# placa-endstops.net
KiCad netlist of a schematic drawn in EAGLE
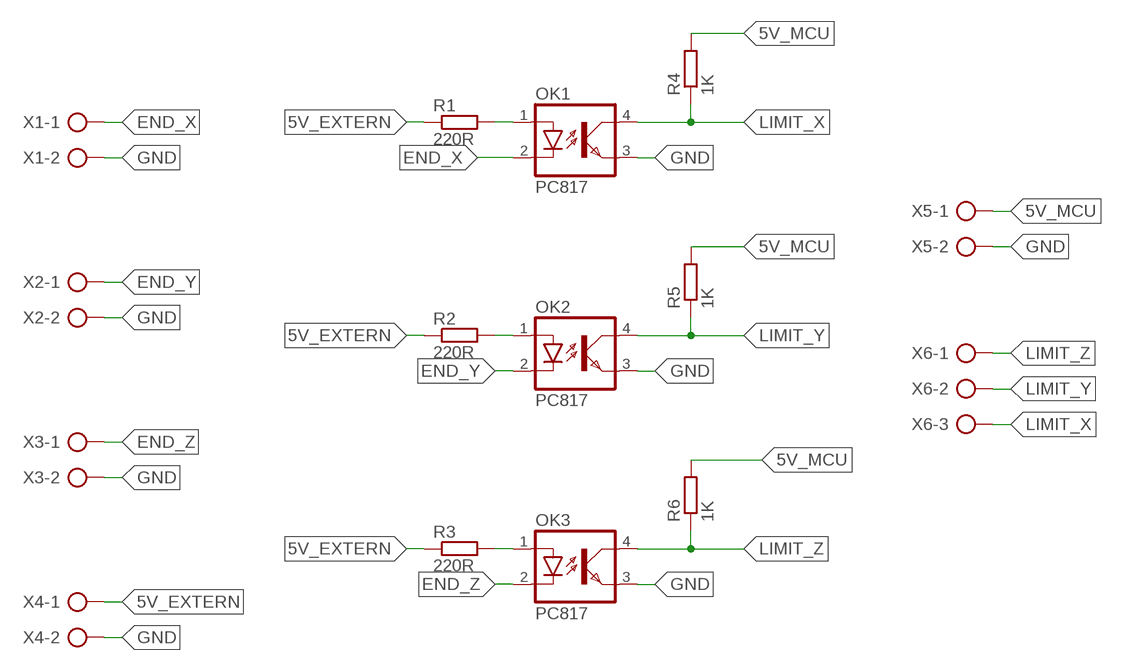
[diagram p0: schematic, sheet 1]

(export (version "E")
  (design (tool "Eeschema 10.0.6"))
  (components
    (comp (ref "OK1")
      (value "PC817")
      (footprint "eagle-import:DIL04")
      (fields (field (name "MPN") "PC817X4J000F"))
      (libsource (lib "eagle-import") (part "PC817"))
    )
    (comp (ref "OK2")
      (value "PC817")
      (footprint "eagle-import:DIL04")
      (fields (field (name "MPN") "PC817X4J000F"))
      (libsource (lib "eagle-import") (part "PC817"))
    )
    (comp (ref "OK3")
      (value "PC817")
      (footprint "eagle-import:DIL04")
      (fields (field (name "MPN") "PC817X4J000F"))
      (libsource (lib "eagle-import") (part "PC817"))
    )
    (comp (ref "R1")
      (value "220R")
      (footprint "eagle-import:0207_10")
      (libsource (lib "eagle-import") (part "R-EU_0207/10"))
    )
    (comp (ref "R2")
      (value "220R")
      (footprint "eagle-import:0207_10")
      (libsource (lib "eagle-import") (part "R-EU_0207/10"))
    )
    (comp (ref "R3")
      (value "220R")
      (footprint "eagle-import:0207_10")
      (libsource (lib "eagle-import") (part "R-EU_0207/10"))
    )
    (comp (ref "R4")
      (value "1K")
      (footprint "eagle-import:0207_10")
      (libsource (lib "eagle-import") (part "R-EU_0207/10"))
    )
    (comp (ref "R5")
      (value "1K")
      (footprint "eagle-import:0207_10")
      (libsource (lib "eagle-import") (part "R-EU_0207/10"))
    )
    (comp (ref "R6")
      (value "1K")
      (footprint "eagle-import:0207_10")
      (libsource (lib "eagle-import") (part "R-EU_0207/10"))
    )
    (comp (ref "X1")
      (value "AK500/2")
      (footprint "eagle-import:AK500_2")
      (libsource (lib "eagle-import") (part "AK500/2"))
    )
    (comp (ref "X2")
      (value "AK500/2")
      (footprint "eagle-import:AK500_2")
      (libsource (lib "eagle-import") (part "AK500/2"))
    )
    (comp (ref "X3")
      (value "AK500/2")
      (footprint "eagle-import:AK500_2")
      (libsource (lib "eagle-import") (part "AK500/2"))
    )
    (comp (ref "X4")
      (value "AK500/2")
      (footprint "eagle-import:AK500_2")
      (libsource (lib "eagle-import") (part "AK500/2"))
    )
    (comp (ref "X5")
      (value "AK500/2")
      (footprint "eagle-import:AK500_2")
      (libsource (lib "eagle-import") (part "AK500/2"))
    )
    (comp (ref "X6")
      (value "AK500/3")
      (footprint "eagle-import:AK500_3")
      (libsource (lib "eagle-import") (part "AK500/3"))
    )
  )
  (nets
    (net (code "1") (name "5V_EXTERN") (class "Default")
      (node (ref "R1") (pin "1") (pinfunction "1_1") (pintype "passive"))
      (node (ref "R2") (pin "1") (pinfunction "1_1") (pintype "passive"))
      (node (ref "R3") (pin "1") (pinfunction "1_1") (pintype "passive"))
      (node (ref "X4") (pin "1") (pinfunction "KL_1") (pintype "passive"))
    )
    (net (code "2") (name "5V_MCU") (class "Default")
      (node (ref "R4") (pin "2") (pinfunction "2_2") (pintype "passive"))
      (node (ref "R5") (pin "2") (pinfunction "2_2") (pintype "passive"))
      (node (ref "R6") (pin "2") (pinfunction "2_2") (pintype "passive"))
      (node (ref "X5") (pin "1") (pinfunction "KL_1") (pintype "passive"))
    )
    (net (code "3") (name "END_X") (class "Default")
      (node (ref "OK1") (pin "2") (pinfunction "C_2") (pintype "passive"))
      (node (ref "X1") (pin "1") (pinfunction "KL_1") (pintype "passive"))
    )
    (net (code "4") (name "END_Y") (class "Default")
      (node (ref "OK2") (pin "2") (pinfunction "C_2") (pintype "passive"))
      (node (ref "X2") (pin "1") (pinfunction "KL_1") (pintype "passive"))
    )
    (net (code "5") (name "END_Z") (class "Default")
      (node (ref "OK3") (pin "2") (pinfunction "C_2") (pintype "passive"))
      (node (ref "X3") (pin "1") (pinfunction "KL_1") (pintype "passive"))
    )
    (net (code "6") (name "GND") (class "Default")
      (node (ref "OK1") (pin "3") (pinfunction "EMIT_3") (pintype "passive"))
      (node (ref "OK2") (pin "3") (pinfunction "EMIT_3") (pintype "passive"))
      (node (ref "OK3") (pin "3") (pinfunction "EMIT_3") (pintype "passive"))
      (node (ref "X1") (pin "2") (pinfunction "KL_2") (pintype "passive"))
      (node (ref "X2") (pin "2") (pinfunction "KL_2") (pintype "passive"))
      (node (ref "X3") (pin "2") (pinfunction "KL_2") (pintype "passive"))
      (node (ref "X4") (pin "2") (pinfunction "KL_2") (pintype "passive"))
      (node (ref "X5") (pin "2") (pinfunction "KL_2") (pintype "passive"))
    )
    (net (code "7") (name "LIMIT_X") (class "Default")
      (node (ref "OK1") (pin "4") (pinfunction "COL_4") (pintype "passive"))
      (node (ref "R4") (pin "1") (pinfunction "1_1") (pintype "passive"))
      (node (ref "X6") (pin "3") (pinfunction "KL_3") (pintype "passive"))
    )
    (net (code "8") (name "LIMIT_Y") (class "Default")
      (node (ref "OK2") (pin "4") (pinfunction "COL_4") (pintype "passive"))
      (node (ref "R5") (pin "1") (pinfunction "1_1") (pintype "passive"))
      (node (ref "X6") (pin "2") (pinfunction "KL_2") (pintype "passive"))
    )
    (net (code "9") (name "LIMIT_Z") (class "Default")
      (node (ref "OK3") (pin "4") (pinfunction "COL_4") (pintype "passive"))
      (node (ref "R6") (pin "1") (pinfunction "1_1") (pintype "passive"))
      (node (ref "X6") (pin "1") (pinfunction "KL_1") (pintype "passive"))
    )
    (net (code "10") (name "Net-(OK1-A)") (class "Default")
      (node (ref "OK1") (pin "1") (pinfunction "A_1") (pintype "passive"))
      (node (ref "R1") (pin "2") (pinfunction "2_2") (pintype "passive"))
    )
    (net (code "11") (name "Net-(OK2-A)") (class "Default")
      (node (ref "OK2") (pin "1") (pinfunction "A_1") (pintype "passive"))
      (node (ref "R2") (pin "2") (pinfunction "2_2") (pintype "passive"))
    )
    (net (code "12") (name "Net-(OK3-A)") (class "Default")
      (node (ref "OK3") (pin "1") (pinfunction "A_1") (pintype "passive"))
      (node (ref "R3") (pin "2") (pinfunction "2_2") (pintype "passive"))
    )
  )
)
